# Connectors.net
KiCad netlist of a schematic drawn in Altium Designer
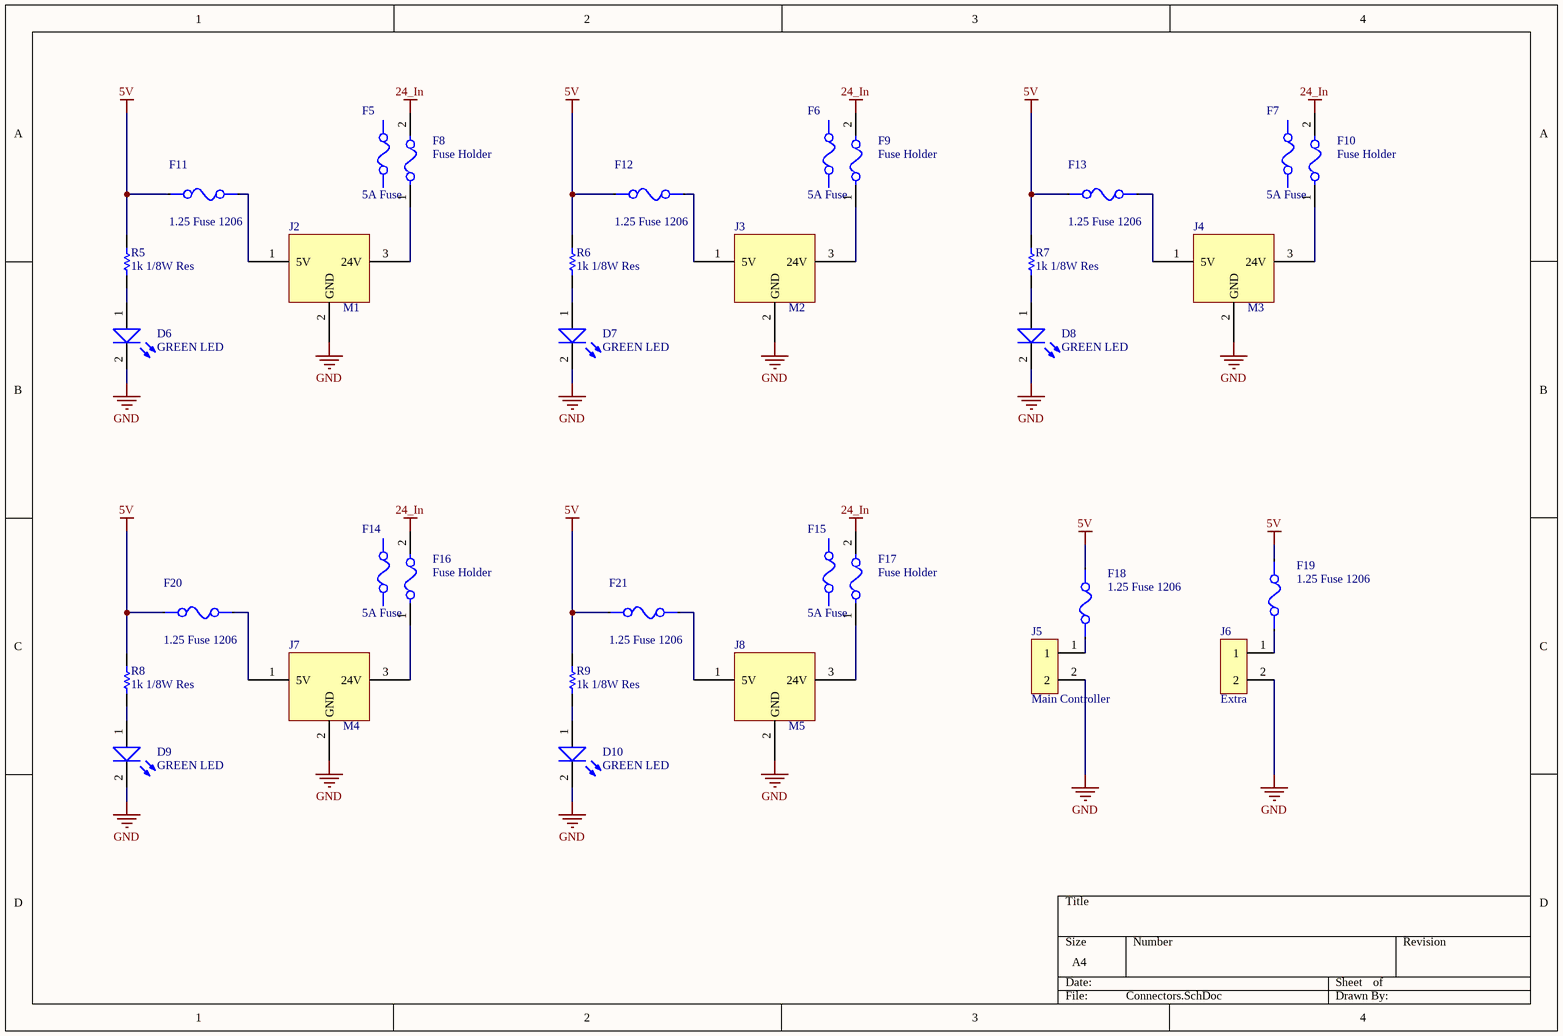
[diagram p0: Connectors.SchDoc]

(export (version "E")
  (design (tool "Eeschema 10.0.6"))
  (components
    (comp (ref "D6")
      (value "GREEN LED")
      (footprint "LED Through Hole")
      (description "Round with Domed Top HLMP-4740 SINGLE COLOR LED Green LED Indication Discrete 6.1mm 5V 2mA 2.3mcd")
      (fields (field (name "MANUFACTURER") "Broadcom") (field (name "MANUFACTURER PART NUMBER") "HLMP-4740"))
      (libsource (lib "Schlib1") (part "HLMP-4740"))
    )
    (comp (ref "D7")
      (value "GREEN LED")
      (footprint "LED Through Hole")
      (description "Round with Domed Top HLMP-4740 SINGLE COLOR LED Green LED Indication Discrete 6.1mm 5V 2mA 2.3mcd")
      (fields (field (name "MANUFACTURER") "Broadcom") (field (name "MANUFACTURER PART NUMBER") "HLMP-4740"))
      (libsource (lib "Schlib1") (part "HLMP-4740"))
    )
    (comp (ref "D8")
      (value "GREEN LED")
      (footprint "LED Through Hole")
      (description "Round with Domed Top HLMP-4740 SINGLE COLOR LED Green LED Indication Discrete 6.1mm 5V 2mA 2.3mcd")
      (fields (field (name "MANUFACTURER") "Broadcom") (field (name "MANUFACTURER PART NUMBER") "HLMP-4740"))
      (libsource (lib "Schlib1") (part "HLMP-4740"))
    )
    (comp (ref "D9")
      (value "GREEN LED")
      (footprint "LED Through Hole")
      (description "Round with Domed Top HLMP-4740 SINGLE COLOR LED Green LED Indication Discrete 6.1mm 5V 2mA 2.3mcd")
      (fields (field (name "MANUFACTURER") "Broadcom") (field (name "MANUFACTURER PART NUMBER") "HLMP-4740"))
      (libsource (lib "Schlib1") (part "HLMP-4740"))
    )
    (comp (ref "D10")
      (value "GREEN LED")
      (footprint "LED Through Hole")
      (description "Round with Domed Top HLMP-4740 SINGLE COLOR LED Green LED Indication Discrete 6.1mm 5V 2mA 2.3mcd")
      (fields (field (name "MANUFACTURER") "Broadcom") (field (name "MANUFACTURER PART NUMBER") "HLMP-4740"))
      (libsource (lib "Schlib1") (part "HLMP-4740"))
    )
    (comp (ref "F5")
      (value "5A Fuse")
      (footprint "5A Fuse")
      (description "Fuse Blade 5A 32V Socket 10.9 X 3.8 X 8.8mm Polyamide 66 Automotive UL")
      (fields
        (field (name "MANUFACTURER") "Littelfuse")
        (field (name "MANUFACTURER PART NUMBER") "0297005.WXNV")
      )
      (libsource (lib "Schlib1") (part "0297005.WXNV"))
    )
    (comp (ref "F6")
      (value "5A Fuse")
      (footprint "5A Fuse")
      (description "Fuse Blade 5A 32V Socket 10.9 X 3.8 X 8.8mm Polyamide 66 Automotive UL")
      (fields
        (field (name "MANUFACTURER") "Littelfuse")
        (field (name "MANUFACTURER PART NUMBER") "0297005.WXNV")
      )
      (libsource (lib "Schlib1") (part "0297005.WXNV"))
    )
    (comp (ref "F7")
      (value "5A Fuse")
      (footprint "5A Fuse")
      (description "Fuse Blade 5A 32V Socket 10.9 X 3.8 X 8.8mm Polyamide 66 Automotive UL")
      (fields
        (field (name "MANUFACTURER") "Littelfuse")
        (field (name "MANUFACTURER PART NUMBER") "0297005.WXNV")
      )
      (libsource (lib "Schlib1") (part "0297005.WXNV"))
    )
    (comp (ref "F8")
      (value "Fuse Holder")
      (footprint "FUSE HOLDER")
      (description "Holder; Fuse; Auto Blade; Mini; 500VAC; 30A; PC Pin Terminal; Nylon 4/6 Holder; Black")
      (fields (field (name "MANUFACTURER") "Keystone") (field (name "MANUFACTURER PART NUMBER") "3568"))
      (libsource (lib "Schlib1") (part "3568"))
    )
    (comp (ref "F9")
      (value "Fuse Holder")
      (footprint "FUSE HOLDER")
      (description "Holder; Fuse; Auto Blade; Mini; 500VAC; 30A; PC Pin Terminal; Nylon 4/6 Holder; Black")
      (fields (field (name "MANUFACTURER") "Keystone") (field (name "MANUFACTURER PART NUMBER") "3568"))
      (libsource (lib "Schlib1") (part "3568"))
    )
    (comp (ref "F10")
      (value "Fuse Holder")
      (footprint "FUSE HOLDER")
      (description "Holder; Fuse; Auto Blade; Mini; 500VAC; 30A; PC Pin Terminal; Nylon 4/6 Holder; Black")
      (fields (field (name "MANUFACTURER") "Keystone") (field (name "MANUFACTURER PART NUMBER") "3568"))
      (libsource (lib "Schlib1") (part "3568"))
    )
    (comp (ref "F11")
      (value "1.25 Fuse 1206")
      (footprint "Fuse 1206")
      (description "Fuse 63V Fa Halogen Free Slim 1206 1.25A/ T&r Rohs Compliant: Yes ¦Littelfuse 04661.25NRHF")
      (fields
        (field (name "MANUFACTURER") "Littelfuse")
        (field (name "MANUFACTURER PART NUMBER") "04661.25NRHF")
      )
      (libsource (lib "Schlib1") (part "04661.25NRHF"))
    )
    (comp (ref "F12")
      (value "1.25 Fuse 1206")
      (footprint "Fuse 1206")
      (description "Fuse 63V Fa Halogen Free Slim 1206 1.25A/ T&r Rohs Compliant: Yes ¦Littelfuse 04661.25NRHF")
      (fields
        (field (name "MANUFACTURER") "Littelfuse")
        (field (name "MANUFACTURER PART NUMBER") "04661.25NRHF")
      )
      (libsource (lib "Schlib1") (part "04661.25NRHF"))
    )
    (comp (ref "F13")
      (value "1.25 Fuse 1206")
      (footprint "Fuse 1206")
      (description "Fuse 63V Fa Halogen Free Slim 1206 1.25A/ T&r Rohs Compliant: Yes ¦Littelfuse 04661.25NRHF")
      (fields
        (field (name "MANUFACTURER") "Littelfuse")
        (field (name "MANUFACTURER PART NUMBER") "04661.25NRHF")
      )
      (libsource (lib "Schlib1") (part "04661.25NRHF"))
    )
    (comp (ref "F14")
      (value "5A Fuse")
      (footprint "5A Fuse")
      (description "Fuse Blade 5A 32V Socket 10.9 X 3.8 X 8.8mm Polyamide 66 Automotive UL")
      (fields
        (field (name "MANUFACTURER") "Littelfuse")
        (field (name "MANUFACTURER PART NUMBER") "0297005.WXNV")
      )
      (libsource (lib "Schlib1") (part "0297005.WXNV"))
    )
    (comp (ref "F15")
      (value "5A Fuse")
      (footprint "5A Fuse")
      (description "Fuse Blade 5A 32V Socket 10.9 X 3.8 X 8.8mm Polyamide 66 Automotive UL")
      (fields
        (field (name "MANUFACTURER") "Littelfuse")
        (field (name "MANUFACTURER PART NUMBER") "0297005.WXNV")
      )
      (libsource (lib "Schlib1") (part "0297005.WXNV"))
    )
    (comp (ref "F16")
      (value "Fuse Holder")
      (footprint "FUSE HOLDER")
      (description "Holder; Fuse; Auto Blade; Mini; 500VAC; 30A; PC Pin Terminal; Nylon 4/6 Holder; Black")
      (fields (field (name "MANUFACTURER") "Keystone") (field (name "MANUFACTURER PART NUMBER") "3568"))
      (libsource (lib "Schlib1") (part "3568"))
    )
    (comp (ref "F17")
      (value "Fuse Holder")
      (footprint "FUSE HOLDER")
      (description "Holder; Fuse; Auto Blade; Mini; 500VAC; 30A; PC Pin Terminal; Nylon 4/6 Holder; Black")
      (fields (field (name "MANUFACTURER") "Keystone") (field (name "MANUFACTURER PART NUMBER") "3568"))
      (libsource (lib "Schlib1") (part "3568"))
    )
    (comp (ref "F18")
      (value "1.25 Fuse 1206")
      (footprint "Fuse 1206")
      (description "Fuse 63V Fa Halogen Free Slim 1206 1.25A/ T&r Rohs Compliant: Yes ¦Littelfuse 04661.25NRHF")
      (fields
        (field (name "MANUFACTURER") "Littelfuse")
        (field (name "MANUFACTURER PART NUMBER") "04661.25NRHF")
      )
      (libsource (lib "Schlib1") (part "04661.25NRHF"))
    )
    (comp (ref "F19")
      (value "1.25 Fuse 1206")
      (footprint "Fuse 1206")
      (description "Fuse 63V Fa Halogen Free Slim 1206 1.25A/ T&r Rohs Compliant: Yes ¦Littelfuse 04661.25NRHF")
      (fields
        (field (name "MANUFACTURER") "Littelfuse")
        (field (name "MANUFACTURER PART NUMBER") "04661.25NRHF")
      )
      (libsource (lib "Schlib1") (part "04661.25NRHF"))
    )
    (comp (ref "F20")
      (value "1.25 Fuse 1206")
      (footprint "Fuse 1206")
      (description "Fuse 63V Fa Halogen Free Slim 1206 1.25A/ T&r Rohs Compliant: Yes ¦Littelfuse 04661.25NRHF")
      (fields
        (field (name "MANUFACTURER") "Littelfuse")
        (field (name "MANUFACTURER PART NUMBER") "04661.25NRHF")
      )
      (libsource (lib "Schlib1") (part "04661.25NRHF"))
    )
    (comp (ref "F21")
      (value "1.25 Fuse 1206")
      (footprint "Fuse 1206")
      (description "Fuse 63V Fa Halogen Free Slim 1206 1.25A/ T&r Rohs Compliant: Yes ¦Littelfuse 04661.25NRHF")
      (fields
        (field (name "MANUFACTURER") "Littelfuse")
        (field (name "MANUFACTURER PART NUMBER") "04661.25NRHF")
      )
      (libsource (lib "Schlib1") (part "04661.25NRHF"))
    )
    (comp (ref "J2")
      (value "M1")
      (footprint "MT-60")
      (fields (field (name "LCSC PART #") "C99176"))
      (libsource (lib "Schlib1") (part "MT-60"))
    )
    (comp (ref "J3")
      (value "M2")
      (footprint "MT-60")
      (fields (field (name "LCSC PART #") "C99176"))
      (libsource (lib "Schlib1") (part "MT-60"))
    )
    (comp (ref "J4")
      (value "M3")
      (footprint "MT-60")
      (fields (field (name "LCSC PART #") "C99176"))
      (libsource (lib "Schlib1") (part "MT-60"))
    )
    (comp (ref "J5")
      (value "Main Controller")
      (footprint "XT60-M")
      (description "Conn DC Power Adapter M/F 2 POS ST 2 Terminal 1 Port")
      (fields (field (name "MANUFACTURER") "SparkFun") (field (name "MANUFACTURER PART NUMBER") "PRT-10474"))
      (libsource (lib "Schlib1") (part "PRT-10474"))
    )
    (comp (ref "J6")
      (value "Extra")
      (footprint "XT60-M")
      (description "Conn DC Power Adapter M/F 2 POS ST 2 Terminal 1 Port")
      (fields (field (name "MANUFACTURER") "SparkFun") (field (name "MANUFACTURER PART NUMBER") "PRT-10474"))
      (libsource (lib "Schlib1") (part "PRT-10474"))
    )
    (comp (ref "J7")
      (value "M4")
      (footprint "MT-60")
      (fields (field (name "LCSC PART #") "C99176"))
      (libsource (lib "Schlib1") (part "MT-60"))
    )
    (comp (ref "J8")
      (value "M5")
      (footprint "MT-60")
      (fields (field (name "LCSC PART #") "C99176"))
      (libsource (lib "Schlib1") (part "MT-60"))
    )
    (comp (ref "R5")
      (value "1k 1/8W Res")
      (footprint "0805 1K Resistor")
      (description "Yageo RC0805FR-071KL SMD Resistor 0603 1k Ohm ±1% Thick Film")
      (fields
        (field (name "MANUFACTURER") "Yageo Group")
        (field (name "MANUFACTURER PART NUMBER") "RC0805FR-071KL")
      )
      (libsource (lib "Schlib1") (part "RC0805FR-071KL"))
    )
    (comp (ref "R6")
      (value "1k 1/8W Res")
      (footprint "0805 1K Resistor")
      (description "Yageo RC0805FR-071KL SMD Resistor 0603 1k Ohm ±1% Thick Film")
      (fields
        (field (name "MANUFACTURER") "Yageo Group")
        (field (name "MANUFACTURER PART NUMBER") "RC0805FR-071KL")
      )
      (libsource (lib "Schlib1") (part "RC0805FR-071KL"))
    )
    (comp (ref "R7")
      (value "1k 1/8W Res")
      (footprint "0805 1K Resistor")
      (description "Yageo RC0805FR-071KL SMD Resistor 0603 1k Ohm ±1% Thick Film")
      (fields
        (field (name "MANUFACTURER") "Yageo Group")
        (field (name "MANUFACTURER PART NUMBER") "RC0805FR-071KL")
      )
      (libsource (lib "Schlib1") (part "RC0805FR-071KL"))
    )
    (comp (ref "R8")
      (value "1k 1/8W Res")
      (footprint "0805 1K Resistor")
      (description "Yageo RC0805FR-071KL SMD Resistor 0603 1k Ohm ±1% Thick Film")
      (fields
        (field (name "MANUFACTURER") "Yageo Group")
        (field (name "MANUFACTURER PART NUMBER") "RC0805FR-071KL")
      )
      (libsource (lib "Schlib1") (part "RC0805FR-071KL"))
    )
    (comp (ref "R9")
      (value "1k 1/8W Res")
      (footprint "0805 1K Resistor")
      (description "Yageo RC0805FR-071KL SMD Resistor 0603 1k Ohm ±1% Thick Film")
      (fields
        (field (name "MANUFACTURER") "Yageo Group")
        (field (name "MANUFACTURER PART NUMBER") "RC0805FR-071KL")
      )
      (libsource (lib "Schlib1") (part "RC0805FR-071KL"))
    )
  )
  (nets
    (net (code "1") (name "5V") (class "Default")
      (node (ref "F11") (pin "1") (pinfunction "1_1") (pintype "passive"))
      (node (ref "F12") (pin "1") (pinfunction "1_1") (pintype "passive"))
      (node (ref "F13") (pin "1") (pinfunction "1_1") (pintype "passive"))
      (node (ref "F18") (pin "2") (pinfunction "2_2") (pintype "passive"))
      (node (ref "F19") (pin "2") (pinfunction "2_2") (pintype "passive"))
      (node (ref "F20") (pin "1") (pinfunction "1_1") (pintype "passive"))
      (node (ref "F21") (pin "1") (pinfunction "1_1") (pintype "passive"))
      (node (ref "R5") (pin "2") (pinfunction "2_2") (pintype "passive"))
      (node (ref "R6") (pin "2") (pinfunction "2_2") (pintype "passive"))
      (node (ref "R7") (pin "2") (pinfunction "2_2") (pintype "passive"))
      (node (ref "R8") (pin "2") (pinfunction "2_2") (pintype "passive"))
      (node (ref "R9") (pin "2") (pinfunction "2_2") (pintype "passive"))
    )
    (net (code "2") (name "24_In") (class "Default")
      (node (ref "F10") (pin "2") (pinfunction "2_2") (pintype "passive"))
      (node (ref "F16") (pin "2") (pinfunction "2_2") (pintype "passive"))
      (node (ref "F17") (pin "2") (pinfunction "2_2") (pintype "passive"))
      (node (ref "F8") (pin "2") (pinfunction "2_2") (pintype "passive"))
      (node (ref "F9") (pin "2") (pinfunction "2_2") (pintype "passive"))
    )
    (net (code "3") (name "GND") (class "Default")
      (node (ref "D10") (pin "2") (pinfunction "K_2") (pintype "passive"))
      (node (ref "D6") (pin "2") (pinfunction "K_2") (pintype "passive"))
      (node (ref "D7") (pin "2") (pinfunction "K_2") (pintype "passive"))
      (node (ref "D8") (pin "2") (pinfunction "K_2") (pintype "passive"))
      (node (ref "D9") (pin "2") (pinfunction "K_2") (pintype "passive"))
      (node (ref "J2") (pin "2") (pinfunction "GND_2") (pintype "passive"))
      (node (ref "J3") (pin "2") (pinfunction "GND_2") (pintype "passive"))
      (node (ref "J4") (pin "2") (pinfunction "GND_2") (pintype "passive"))
      (node (ref "J5") (pin "2") (pinfunction "2_2") (pintype "passive"))
      (node (ref "J6") (pin "2") (pinfunction "2_2") (pintype "passive"))
      (node (ref "J7") (pin "2") (pinfunction "GND_2") (pintype "passive"))
      (node (ref "J8") (pin "2") (pinfunction "GND_2") (pintype "passive"))
    )
    (net (code "4") (name "Net-(D6-A)") (class "Default")
      (node (ref "D6") (pin "1") (pinfunction "A_1") (pintype "passive"))
      (node (ref "R5") (pin "1") (pinfunction "1_1") (pintype "passive"))
    )
    (net (code "5") (name "Net-(D7-A)") (class "Default")
      (node (ref "D7") (pin "1") (pinfunction "A_1") (pintype "passive"))
      (node (ref "R6") (pin "1") (pinfunction "1_1") (pintype "passive"))
    )
    (net (code "6") (name "Net-(D8-A)") (class "Default")
      (node (ref "D8") (pin "1") (pinfunction "A_1") (pintype "passive"))
      (node (ref "R7") (pin "1") (pinfunction "1_1") (pintype "passive"))
    )
    (net (code "7") (name "Net-(D9-A)") (class "Default")
      (node (ref "D9") (pin "1") (pinfunction "A_1") (pintype "passive"))
      (node (ref "R8") (pin "1") (pinfunction "1_1") (pintype "passive"))
    )
    (net (code "8") (name "Net-(D10-A)") (class "Default")
      (node (ref "D10") (pin "1") (pinfunction "A_1") (pintype "passive"))
      (node (ref "R9") (pin "1") (pinfunction "1_1") (pintype "passive"))
    )
    (net (code "9") (name "Net-(F18-Pad1)") (class "Default")
      (node (ref "F18") (pin "1") (pinfunction "1_1") (pintype "passive"))
      (node (ref "J5") (pin "1") (pinfunction "1_1") (pintype "passive"))
    )
    (net (code "10") (name "Net-(F19-Pad1)") (class "Default")
      (node (ref "F19") (pin "1") (pinfunction "1_1") (pintype "passive"))
      (node (ref "J6") (pin "1") (pinfunction "1_1") (pintype "passive"))
    )
    (net (code "11") (name "Net-(J2-5V)") (class "Default")
      (node (ref "F11") (pin "2") (pinfunction "2_2") (pintype "passive"))
      (node (ref "J2") (pin "1") (pinfunction "5V_1") (pintype "passive"))
    )
    (net (code "12") (name "Net-(J2-24V)") (class "Default")
      (node (ref "F8") (pin "1") (pinfunction "1_1") (pintype "passive"))
      (node (ref "J2") (pin "3") (pinfunction "24V_3") (pintype "passive"))
    )
    (net (code "13") (name "Net-(J3-5V)") (class "Default")
      (node (ref "F12") (pin "2") (pinfunction "2_2") (pintype "passive"))
      (node (ref "J3") (pin "1") (pinfunction "5V_1") (pintype "passive"))
    )
    (net (code "14") (name "Net-(J3-24V)") (class "Default")
      (node (ref "F9") (pin "1") (pinfunction "1_1") (pintype "passive"))
      (node (ref "J3") (pin "3") (pinfunction "24V_3") (pintype "passive"))
    )
    (net (code "15") (name "Net-(J4-5V)") (class "Default")
      (node (ref "F13") (pin "2") (pinfunction "2_2") (pintype "passive"))
      (node (ref "J4") (pin "1") (pinfunction "5V_1") (pintype "passive"))
    )
    (net (code "16") (name "Net-(J4-24V)") (class "Default")
      (node (ref "F10") (pin "1") (pinfunction "1_1") (pintype "passive"))
      (node (ref "J4") (pin "3") (pinfunction "24V_3") (pintype "passive"))
    )
    (net (code "17") (name "Net-(J7-5V)") (class "Default")
      (node (ref "F20") (pin "2") (pinfunction "2_2") (pintype "passive"))
      (node (ref "J7") (pin "1") (pinfunction "5V_1") (pintype "passive"))
    )
    (net (code "18") (name "Net-(J7-24V)") (class "Default")
      (node (ref "F16") (pin "1") (pinfunction "1_1") (pintype "passive"))
      (node (ref "J7") (pin "3") (pinfunction "24V_3") (pintype "passive"))
    )
    (net (code "19") (name "Net-(J8-5V)") (class "Default")
      (node (ref "F21") (pin "2") (pinfunction "2_2") (pintype "passive"))
      (node (ref "J8") (pin "1") (pinfunction "5V_1") (pintype "passive"))
    )
    (net (code "20") (name "Net-(J8-24V)") (class "Default")
      (node (ref "F17") (pin "1") (pinfunction "1_1") (pintype "passive"))
      (node (ref "J8") (pin "3") (pinfunction "24V_3") (pintype "passive"))
    )
  )
)
